# schematic.net
KiCad netlist of a schematic drawn in EAGLE
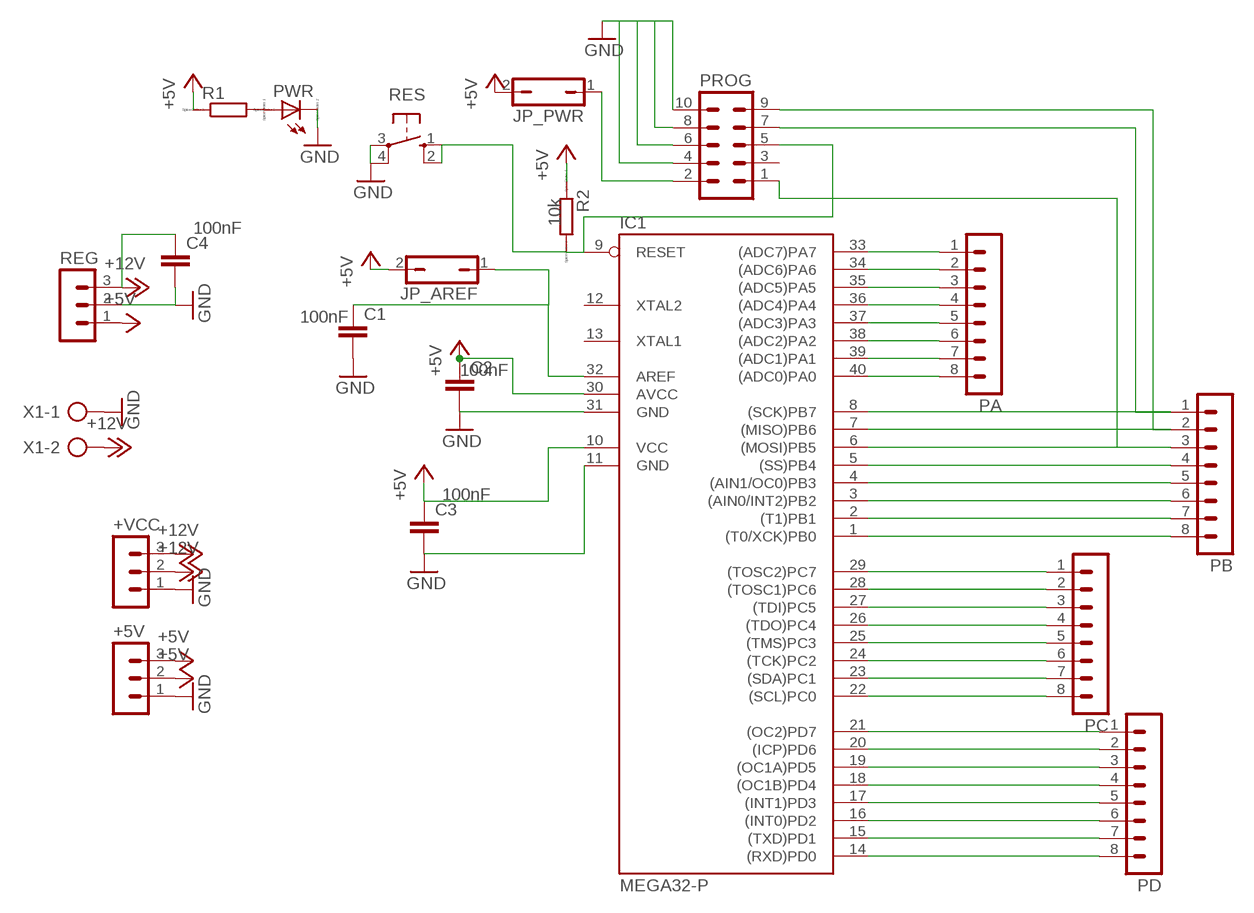
[diagram p0: schematic, sheet 1]

(export (version "E")
  (design (tool "Eeschema 10.0.6"))
  (components
    (comp (ref "+5V")
      (value "MA03-1")
      (footprint "eagle-import:MA03-1")
      (libsource (lib "eagle-import") (part "MA03-1"))
    )
    (comp (ref "+VCC")
      (value "MA03-1")
      (footprint "eagle-import:MA03-1")
      (libsource (lib "eagle-import") (part "MA03-1"))
    )
    (comp (ref "C1")
      (value "C2,5-3")
      (footprint "eagle-import:C2.5-3")
      (fields (field (name "CAPACITY") "100nF"))
      (libsource (lib "eagle-import") (part "C2,5-3"))
    )
    (comp (ref "C2")
      (value "C2,5-3")
      (footprint "eagle-import:C2.5-3")
      (fields (field (name "CAPACITY") "100nF"))
      (libsource (lib "eagle-import") (part "C2,5-3"))
    )
    (comp (ref "C3")
      (value "C2,5-3")
      (footprint "eagle-import:C2.5-3")
      (fields (field (name "CAPACITY") "100nF"))
      (libsource (lib "eagle-import") (part "C2,5-3"))
    )
    (comp (ref "C4")
      (value "C2,5-3")
      (footprint "eagle-import:C2.5-3")
      (fields (field (name "CAPACITY") "100nF"))
      (libsource (lib "eagle-import") (part "C2,5-3"))
    )
    (comp (ref "IC1")
      (value "MEGA32-P")
      (footprint "eagle-import:DIL40")
      (fields (field (name "MPN") "ATMEGA32-16PU"))
      (libsource (lib "eagle-import") (part "MEGA32-P"))
    )
    (comp (ref "JP_AREF")
      (value "JP1Q")
      (footprint "eagle-import:JP1")
      (libsource (lib "eagle-import") (part "JP1Q"))
    )
    (comp (ref "JP_PWR")
      (value "JP1Q")
      (footprint "eagle-import:JP1")
      (libsource (lib "eagle-import") (part "JP1Q"))
    )
    (comp (ref "PA")
      (value "MA08-1")
      (footprint "eagle-import:MA08-1")
      (libsource (lib "eagle-import") (part "MA08-1"))
    )
    (comp (ref "PB")
      (value "MA08-1")
      (footprint "eagle-import:MA08-1")
      (libsource (lib "eagle-import") (part "MA08-1"))
    )
    (comp (ref "PC")
      (value "MA08-1")
      (footprint "eagle-import:MA08-1")
      (libsource (lib "eagle-import") (part "MA08-1"))
    )
    (comp (ref "PD")
      (value "MA08-1")
      (footprint "eagle-import:MA08-1")
      (libsource (lib "eagle-import") (part "MA08-1"))
    )
    (comp (ref "PROG")
      (value "MA05-2")
      (footprint "eagle-import:MA05-2")
      (libsource (lib "eagle-import") (part "MA05-2"))
    )
    (comp (ref "PWR")
      (value "LED_E")
      (footprint "eagle-import:LED_1206")
      (libsource (lib "eagle-import") (part "LED_E"))
    )
    (comp (ref "R1")
      (value "RR1206")
      (footprint "eagle-import:R1206")
      (libsource (lib "eagle-import") (part "RR1206"))
    )
    (comp (ref "R2")
      (value "RR1206")
      (footprint "eagle-import:R1206")
      (fields (field (name "SPICEMODEL") "NONE") (field (name "SPICEMODEL_1") "10k"))
      (libsource (lib "eagle-import") (part "RR1206"))
    )
    (comp (ref "REG")
      (value "MA03-1")
      (footprint "eagle-import:MA03-1")
      (libsource (lib "eagle-import") (part "MA03-1"))
    )
    (comp (ref "RES")
      (value "10-XX")
      (footprint "eagle-import:B3F-10XX")
      (fields (field (name "MPN") "B3F-1000"))
      (libsource (lib "eagle-import") (part "10-XX"))
    )
    (comp (ref "X1")
      (value "AK300/2")
      (footprint "eagle-import:AK300_2")
      (libsource (lib "eagle-import") (part "AK300/2"))
    )
  )
  (nets
    (net (code "1") (name "+5V") (class "Default")
      (node (ref "+5V") (pin "2") (pinfunction "2_2") (pintype "passive"))
      (node (ref "+5V") (pin "3") (pinfunction "3_3") (pintype "passive"))
      (node (ref "C2") (pin "1") (pinfunction "1_1") (pintype "passive"))
      (node (ref "C3") (pin "1") (pinfunction "1_1") (pintype "passive"))
      (node (ref "IC1") (pin "10") (pinfunction "VCC_10") (pintype "power_in"))
      (node (ref "IC1") (pin "30") (pinfunction "AVCC_30") (pintype "power_in"))
      (node (ref "JP_AREF") (pin "2") (pinfunction "2_2") (pintype "passive"))
      (node (ref "JP_PWR") (pin "2") (pinfunction "2_2") (pintype "passive"))
      (node (ref "R1") (pin "1") (pinfunction "1_1") (pintype "passive"))
      (node (ref "R2") (pin "1") (pinfunction "1_1") (pintype "passive"))
      (node (ref "REG") (pin "1") (pinfunction "1_1") (pintype "passive"))
    )
    (net (code "2") (name "+12V") (class "Default")
      (node (ref "+VCC") (pin "2") (pinfunction "2_2") (pintype "passive"))
      (node (ref "+VCC") (pin "3") (pinfunction "3_3") (pintype "passive"))
      (node (ref "C4") (pin "1") (pinfunction "1_1") (pintype "passive"))
      (node (ref "REG") (pin "3") (pinfunction "3_3") (pintype "passive"))
      (node (ref "X1") (pin "2") (pinfunction "KL_2") (pintype "passive"))
    )
    (net (code "3") (name "GND") (class "Default")
      (node (ref "+5V") (pin "1") (pinfunction "1_1") (pintype "passive"))
      (node (ref "+VCC") (pin "1") (pinfunction "1_1") (pintype "passive"))
      (node (ref "C1") (pin "2") (pinfunction "2_2") (pintype "passive"))
      (node (ref "C2") (pin "2") (pinfunction "2_2") (pintype "passive"))
      (node (ref "C3") (pin "2") (pinfunction "2_2") (pintype "passive"))
      (node (ref "C4") (pin "2") (pinfunction "2_2") (pintype "passive"))
      (node (ref "IC1") (pin "11") (pinfunction "GND_11") (pintype "power_in"))
      (node (ref "IC1") (pin "31") (pinfunction "GND_31") (pintype "power_in"))
      (node (ref "PROG") (pin "10") (pinfunction "10_10") (pintype "passive"))
      (node (ref "PROG") (pin "4") (pinfunction "4_4") (pintype "passive"))
      (node (ref "PROG") (pin "6") (pinfunction "6_6") (pintype "passive"))
      (node (ref "PROG") (pin "8") (pinfunction "8_8") (pintype "passive"))
      (node (ref "PWR") (pin "C") (pinfunction "C_C") (pintype "passive"))
      (node (ref "REG") (pin "2") (pinfunction "2_2") (pintype "passive"))
      (node (ref "RES") (pin "3") (pinfunction "P_3") (pintype "passive"))
      (node (ref "RES") (pin "4") (pinfunction "P1_4") (pintype "passive"))
      (node (ref "X1") (pin "1") (pinfunction "KL_1") (pintype "passive"))
    )
    (net (code "4") (name "Net-(IC1-(ADC0)PA0)") (class "Default")
      (node (ref "IC1") (pin "40") (pinfunction "(ADC0)PA0_40") (pintype "bidirectional"))
      (node (ref "PA") (pin "8") (pinfunction "8_8") (pintype "passive"))
    )
    (net (code "5") (name "Net-(IC1-(ADC1)PA1)") (class "Default")
      (node (ref "IC1") (pin "39") (pinfunction "(ADC1)PA1_39") (pintype "bidirectional"))
      (node (ref "PA") (pin "7") (pinfunction "7_7") (pintype "passive"))
    )
    (net (code "6") (name "Net-(IC1-(ADC2)PA2)") (class "Default")
      (node (ref "IC1") (pin "38") (pinfunction "(ADC2)PA2_38") (pintype "bidirectional"))
      (node (ref "PA") (pin "6") (pinfunction "6_6") (pintype "passive"))
    )
    (net (code "7") (name "Net-(IC1-(ADC3)PA3)") (class "Default")
      (node (ref "IC1") (pin "37") (pinfunction "(ADC3)PA3_37") (pintype "bidirectional"))
      (node (ref "PA") (pin "5") (pinfunction "5_5") (pintype "passive"))
    )
    (net (code "8") (name "Net-(IC1-(ADC4)PA4)") (class "Default")
      (node (ref "IC1") (pin "36") (pinfunction "(ADC4)PA4_36") (pintype "bidirectional"))
      (node (ref "PA") (pin "4") (pinfunction "4_4") (pintype "passive"))
    )
    (net (code "9") (name "Net-(IC1-(ADC5)PA5)") (class "Default")
      (node (ref "IC1") (pin "35") (pinfunction "(ADC5)PA5_35") (pintype "bidirectional"))
      (node (ref "PA") (pin "3") (pinfunction "3_3") (pintype "passive"))
    )
    (net (code "10") (name "Net-(IC1-(ADC6)PA6)") (class "Default")
      (node (ref "IC1") (pin "34") (pinfunction "(ADC6)PA6_34") (pintype "bidirectional"))
      (node (ref "PA") (pin "2") (pinfunction "2_2") (pintype "passive"))
    )
    (net (code "11") (name "Net-(IC1-(ADC7)PA7)") (class "Default")
      (node (ref "IC1") (pin "33") (pinfunction "(ADC7)PA7_33") (pintype "bidirectional"))
      (node (ref "PA") (pin "1") (pinfunction "1_1") (pintype "passive"))
    )
    (net (code "12") (name "Net-(IC1-(AIN0{slash}INT2)PB2)") (class "Default")
      (node (ref "IC1") (pin "3") (pinfunction "(AIN0/INT2)PB2_3") (pintype "bidirectional"))
      (node (ref "PB") (pin "6") (pinfunction "6_6") (pintype "passive"))
    )
    (net (code "13") (name "Net-(IC1-(AIN1{slash}OC0)PB3)") (class "Default")
      (node (ref "IC1") (pin "4") (pinfunction "(AIN1/OC0)PB3_4") (pintype "bidirectional"))
      (node (ref "PB") (pin "5") (pinfunction "5_5") (pintype "passive"))
    )
    (net (code "14") (name "Net-(IC1-(ICP)PD6)") (class "Default")
      (node (ref "IC1") (pin "20") (pinfunction "(ICP)PD6_20") (pintype "bidirectional"))
      (node (ref "PD") (pin "2") (pinfunction "2_2") (pintype "passive"))
    )
    (net (code "15") (name "Net-(IC1-(INT0)PD2)") (class "Default")
      (node (ref "IC1") (pin "16") (pinfunction "(INT0)PD2_16") (pintype "bidirectional"))
      (node (ref "PD") (pin "6") (pinfunction "6_6") (pintype "passive"))
    )
    (net (code "16") (name "Net-(IC1-(INT1)PD3)") (class "Default")
      (node (ref "IC1") (pin "17") (pinfunction "(INT1)PD3_17") (pintype "bidirectional"))
      (node (ref "PD") (pin "5") (pinfunction "5_5") (pintype "passive"))
    )
    (net (code "17") (name "Net-(IC1-(MISO)PB6)") (class "Default")
      (node (ref "IC1") (pin "7") (pinfunction "(MISO)PB6_7") (pintype "bidirectional"))
      (node (ref "PB") (pin "2") (pinfunction "2_2") (pintype "passive"))
      (node (ref "PROG") (pin "9") (pinfunction "9_9") (pintype "passive"))
    )
    (net (code "18") (name "Net-(IC1-(MOSI)PB5)") (class "Default")
      (node (ref "IC1") (pin "6") (pinfunction "(MOSI)PB5_6") (pintype "bidirectional"))
      (node (ref "PB") (pin "3") (pinfunction "3_3") (pintype "passive"))
      (node (ref "PROG") (pin "1") (pinfunction "1_1") (pintype "passive"))
    )
    (net (code "19") (name "Net-(IC1-(OC1A)PD5)") (class "Default")
      (node (ref "IC1") (pin "19") (pinfunction "(OC1A)PD5_19") (pintype "bidirectional"))
      (node (ref "PD") (pin "3") (pinfunction "3_3") (pintype "passive"))
    )
    (net (code "20") (name "Net-(IC1-(OC1B)PD4)") (class "Default")
      (node (ref "IC1") (pin "18") (pinfunction "(OC1B)PD4_18") (pintype "bidirectional"))
      (node (ref "PD") (pin "4") (pinfunction "4_4") (pintype "passive"))
    )
    (net (code "21") (name "Net-(IC1-(OC2)PD7)") (class "Default")
      (node (ref "IC1") (pin "21") (pinfunction "(OC2)PD7_21") (pintype "bidirectional"))
      (node (ref "PD") (pin "1") (pinfunction "1_1") (pintype "passive"))
    )
    (net (code "22") (name "Net-(IC1-(RXD)PD0)") (class "Default")
      (node (ref "IC1") (pin "14") (pinfunction "(RXD)PD0_14") (pintype "bidirectional"))
      (node (ref "PD") (pin "8") (pinfunction "8_8") (pintype "passive"))
    )
    (net (code "23") (name "Net-(IC1-(SCK)PB7)") (class "Default")
      (node (ref "IC1") (pin "8") (pinfunction "(SCK)PB7_8") (pintype "bidirectional"))
      (node (ref "PB") (pin "1") (pinfunction "1_1") (pintype "passive"))
      (node (ref "PROG") (pin "7") (pinfunction "7_7") (pintype "passive"))
    )
    (net (code "24") (name "Net-(IC1-(SCL)PC0)") (class "Default")
      (node (ref "IC1") (pin "22") (pinfunction "(SCL)PC0_22") (pintype "bidirectional"))
      (node (ref "PC") (pin "8") (pinfunction "8_8") (pintype "passive"))
    )
    (net (code "25") (name "Net-(IC1-(SDA)PC1)") (class "Default")
      (node (ref "IC1") (pin "23") (pinfunction "(SDA)PC1_23") (pintype "bidirectional"))
      (node (ref "PC") (pin "7") (pinfunction "7_7") (pintype "passive"))
    )
    (net (code "26") (name "Net-(IC1-(SS)PB4)") (class "Default")
      (node (ref "IC1") (pin "5") (pinfunction "(SS)PB4_5") (pintype "bidirectional"))
      (node (ref "PB") (pin "4") (pinfunction "4_4") (pintype "passive"))
    )
    (net (code "27") (name "Net-(IC1-(T0{slash}XCK)PB0)") (class "Default")
      (node (ref "IC1") (pin "1") (pinfunction "(T0/XCK)PB0_1") (pintype "bidirectional"))
      (node (ref "PB") (pin "8") (pinfunction "8_8") (pintype "passive"))
    )
    (net (code "28") (name "Net-(IC1-(T1)PB1)") (class "Default")
      (node (ref "IC1") (pin "2") (pinfunction "(T1)PB1_2") (pintype "bidirectional"))
      (node (ref "PB") (pin "7") (pinfunction "7_7") (pintype "passive"))
    )
    (net (code "29") (name "Net-(IC1-(TCK)PC2)") (class "Default")
      (node (ref "IC1") (pin "24") (pinfunction "(TCK)PC2_24") (pintype "bidirectional"))
      (node (ref "PC") (pin "6") (pinfunction "6_6") (pintype "passive"))
    )
    (net (code "30") (name "Net-(IC1-(TDI)PC5)") (class "Default")
      (node (ref "IC1") (pin "27") (pinfunction "(TDI)PC5_27") (pintype "bidirectional"))
      (node (ref "PC") (pin "3") (pinfunction "3_3") (pintype "passive"))
    )
    (net (code "31") (name "Net-(IC1-(TDO)PC4)") (class "Default")
      (node (ref "IC1") (pin "26") (pinfunction "(TDO)PC4_26") (pintype "bidirectional"))
      (node (ref "PC") (pin "4") (pinfunction "4_4") (pintype "passive"))
    )
    (net (code "32") (name "Net-(IC1-(TMS)PC3)") (class "Default")
      (node (ref "IC1") (pin "25") (pinfunction "(TMS)PC3_25") (pintype "bidirectional"))
      (node (ref "PC") (pin "5") (pinfunction "5_5") (pintype "passive"))
    )
    (net (code "33") (name "Net-(IC1-(TOSC1)PC6)") (class "Default")
      (node (ref "IC1") (pin "28") (pinfunction "(TOSC1)PC6_28") (pintype "bidirectional"))
      (node (ref "PC") (pin "2") (pinfunction "2_2") (pintype "passive"))
    )
    (net (code "34") (name "Net-(IC1-(TOSC2)PC7)") (class "Default")
      (node (ref "IC1") (pin "29") (pinfunction "(TOSC2)PC7_29") (pintype "bidirectional"))
      (node (ref "PC") (pin "1") (pinfunction "1_1") (pintype "passive"))
    )
    (net (code "35") (name "Net-(IC1-(TXD)PD1)") (class "Default")
      (node (ref "IC1") (pin "15") (pinfunction "(TXD)PD1_15") (pintype "bidirectional"))
      (node (ref "PD") (pin "7") (pinfunction "7_7") (pintype "passive"))
    )
    (net (code "36") (name "Net-(IC1-AREF)") (class "Default")
      (node (ref "C1") (pin "1") (pinfunction "1_1") (pintype "passive"))
      (node (ref "IC1") (pin "32") (pinfunction "AREF_32") (pintype "passive"))
      (node (ref "JP_AREF") (pin "1") (pinfunction "1_1") (pintype "passive"))
    )
    (net (code "37") (name "Net-(IC1-RESET)") (class "Default")
      (node (ref "IC1") (pin "9") (pinfunction "RESET_9") (pintype "input"))
      (node (ref "PROG") (pin "5") (pinfunction "5_5") (pintype "passive"))
      (node (ref "R2") (pin "2") (pinfunction "2_2") (pintype "passive"))
      (node (ref "RES") (pin "1") (pinfunction "S_1") (pintype "passive"))
      (node (ref "RES") (pin "2") (pinfunction "S1_2") (pintype "passive"))
    )
    (net (code "38") (name "Net-(JP_PWR-Pad1)") (class "Default")
      (node (ref "JP_PWR") (pin "1") (pinfunction "1_1") (pintype "passive"))
      (node (ref "PROG") (pin "2") (pinfunction "2_2") (pintype "passive"))
    )
    (net (code "39") (name "Net-(PWR-PadA)") (class "Default")
      (node (ref "PWR") (pin "A") (pinfunction "A_A") (pintype "passive"))
      (node (ref "R1") (pin "2") (pinfunction "2_2") (pintype "passive"))
    )
    (net (code "40") (name "unconnected-(IC1-XTAL1-Pad13)") (class "Default")
      (node (ref "IC1") (pin "13") (pinfunction "XTAL1_13") (pintype "bidirectional"))
    )
    (net (code "41") (name "unconnected-(IC1-XTAL2-Pad12)") (class "Default")
      (node (ref "IC1") (pin "12") (pinfunction "XTAL2_12") (pintype "bidirectional"))
    )
    (net (code "42") (name "unconnected-(PROG-Pad3)") (class "Default")
      (node (ref "PROG") (pin "3") (pinfunction "3_3") (pintype "passive"))
    )
  )
)
